# THAT15xx_lean.net
KiCad netlist of a schematic drawn in EAGLE
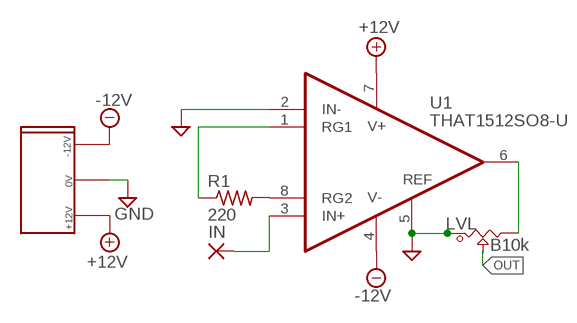
[diagram p0: schematic, sheet 1]

(export (version "E")
  (design (tool "Eeschema 10.0.6"))
  (components
    (comp (ref "IN")
      (value "WIREPADSMD5-1,8")
      (footprint "eagle-import:5-1,8")
      (libsource (lib "eagle-import") (part "WIREPADSMD5-1,8"))
    )
    (comp (ref "LVL")
      (value "B10k")
      (footprint "eagle-import:POT_9MM_SMD")
      (libsource (lib "eagle-import") (part "POT_9MM_SMD"))
    )
    (comp (ref "R1")
      (value "220")
      (footprint "eagle-import:R0603")
      (libsource (lib "eagle-import") (part "R-US_R0603"))
    )
    (comp (ref "U$1")
      (value "EURO_POW_CEH")
      (footprint "eagle-import:EURO_POW_CEH")
      (libsource (lib "eagle-import") (part "EURO_POW_CEH"))
    )
    (comp (ref "U1")
      (value "THAT1512SO8-U")
      (footprint "eagle-import:SO08")
      (libsource (lib "eagle-import") (part "THAT1512SO8-U"))
    )
  )
  (nets
    (net (code "1") (name "+12V") (class "Default")
      (node (ref "U$1") (pin "+12V") (pinfunction "+12V_+12V") (pintype "bidirectional"))
      (node (ref "U1") (pin "7") (pinfunction "V+_7") (pintype "power_in"))
    )
    (net (code "2") (name "-12V") (class "Default")
      (node (ref "U$1") (pin "-12V") (pinfunction "-12V_-12V") (pintype "bidirectional"))
      (node (ref "U1") (pin "4") (pinfunction "V-_4") (pintype "power_in"))
    )
    (net (code "3") (name "GND") (class "Default")
      (node (ref "LVL") (pin "1") (pinfunction "1_1") (pintype "bidirectional"))
      (node (ref "U$1") (pin "GND") (pinfunction "GND_GND") (pintype "bidirectional"))
      (node (ref "U1") (pin "2") (pinfunction "IN-_2") (pintype "input"))
      (node (ref "U1") (pin "5") (pinfunction "REF_5") (pintype "input"))
    )
    (net (code "4") (name "Net-(IN-P)") (class "Default")
      (node (ref "IN") (pin "1") (pinfunction "P_1") (pintype "passive"))
      (node (ref "U1") (pin "3") (pinfunction "IN+_3") (pintype "input"))
    )
    (net (code "5") (name "Net-(U1-OUT)") (class "Default")
      (node (ref "LVL") (pin "3") (pinfunction "3_3") (pintype "bidirectional"))
      (node (ref "U1") (pin "6") (pinfunction "OUT_6") (pintype "output"))
    )
    (net (code "6") (name "Net-(U1-RG1)") (class "Default")
      (node (ref "R1") (pin "1") (pinfunction "1_1") (pintype "passive"))
      (node (ref "U1") (pin "1") (pinfunction "RG1_1") (pintype "input"))
    )
    (net (code "7") (name "Net-(U1-RG2)") (class "Default")
      (node (ref "R1") (pin "2") (pinfunction "2_2") (pintype "passive"))
      (node (ref "U1") (pin "8") (pinfunction "RG2_8") (pintype "input"))
    )
    (net (code "8") (name "OUT") (class "Default")
      (node (ref "LVL") (pin "2") (pinfunction "2_2") (pintype "bidirectional"))
    )
  )
)
